# Phaser_1.net
KiCad netlist of a schematic drawn in Altium Designer
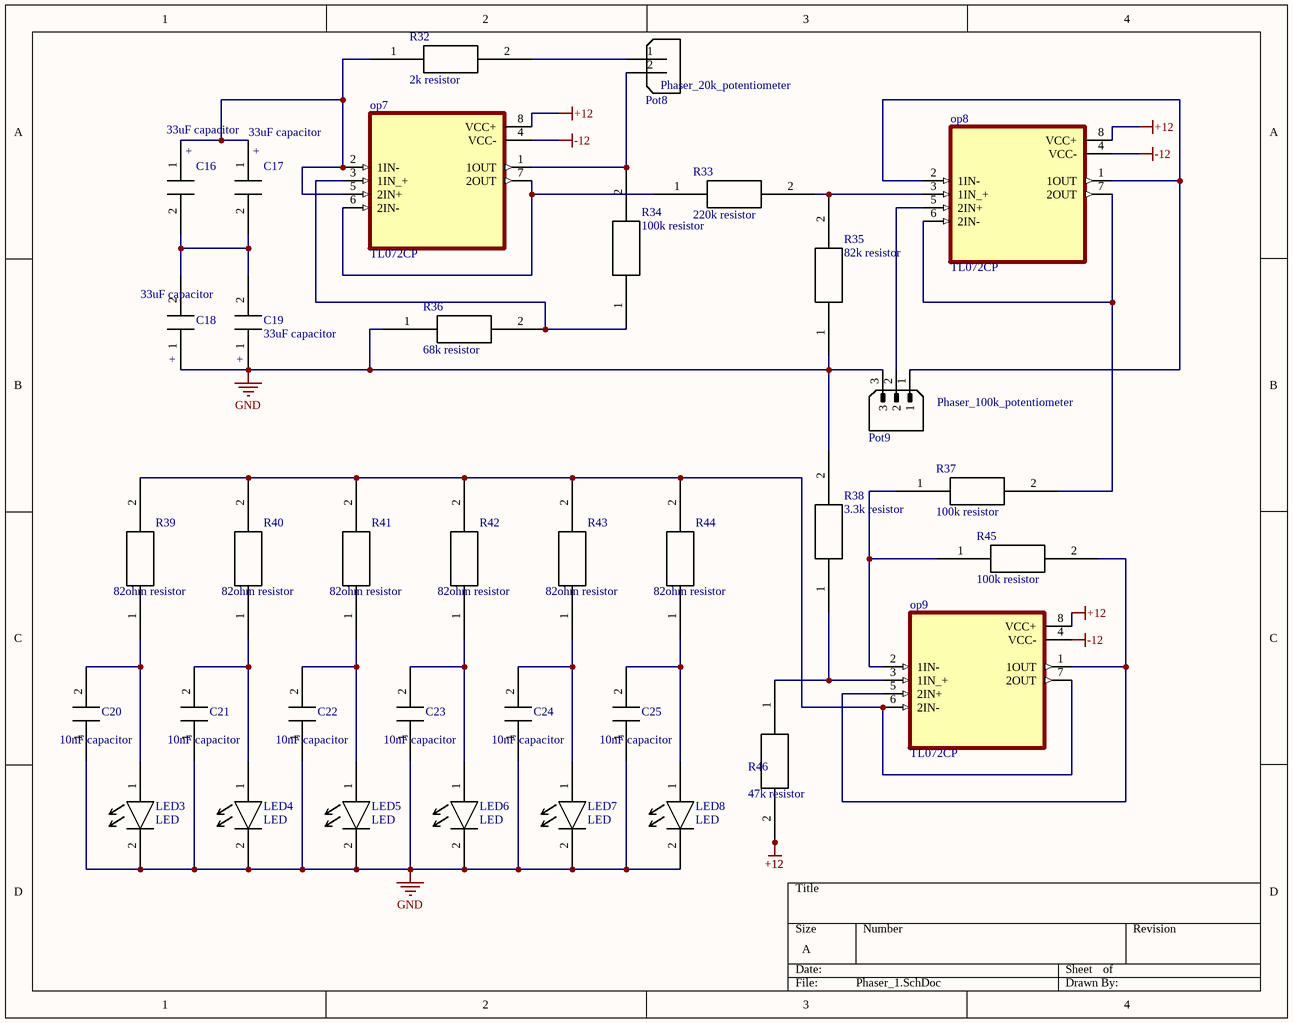
[diagram p0: Phaser_1.SchDoc]

(export (version "E")
  (design (tool "Eeschema 10.0.6"))
  (components
    (comp (ref "C16")
      (value "33uF capacitor")
      (footprint "33uF")
      (libsource (lib "Analog_Project_Schlib") (part "33uF capacitor"))
    )
    (comp (ref "C17")
      (value "33uF capacitor")
      (footprint "33uF")
      (libsource (lib "Analog_Project_Schlib") (part "33uF capacitor"))
    )
    (comp (ref "C18")
      (value "33uF capacitor")
      (footprint "33uF")
      (libsource (lib "Analog_Project_Schlib") (part "33uF capacitor"))
    )
    (comp (ref "C19")
      (value "33uF capacitor")
      (footprint "33uF")
      (libsource (lib "Analog_Project_Schlib") (part "33uF capacitor"))
    )
    (comp (ref "C20")
      (value "10nF capacitor")
      (footprint "10nF")
      (libsource (lib "Analog_Project_Schlib") (part "10nF capacitor"))
    )
    (comp (ref "C21")
      (value "10nF capacitor")
      (footprint "10nF")
      (libsource (lib "Analog_Project_Schlib") (part "10nF capacitor"))
    )
    (comp (ref "C22")
      (value "10nF capacitor")
      (footprint "10nF")
      (libsource (lib "Analog_Project_Schlib") (part "10nF capacitor"))
    )
    (comp (ref "C23")
      (value "10nF capacitor")
      (footprint "10nF")
      (libsource (lib "Analog_Project_Schlib") (part "10nF capacitor"))
    )
    (comp (ref "C24")
      (value "10nF capacitor")
      (footprint "10nF")
      (libsource (lib "Analog_Project_Schlib") (part "10nF capacitor"))
    )
    (comp (ref "C25")
      (value "10nF capacitor")
      (footprint "10nF")
      (libsource (lib "Analog_Project_Schlib") (part "10nF capacitor"))
    )
    (comp (ref "LED3") (value "LED") (footprint "LED") (libsource (lib "Analog_Project_Schlib") (part "LED")))
    (comp (ref "LED4") (value "LED") (footprint "LED") (libsource (lib "Analog_Project_Schlib") (part "LED")))
    (comp (ref "LED5") (value "LED") (footprint "LED") (libsource (lib "Analog_Project_Schlib") (part "LED")))
    (comp (ref "LED6") (value "LED") (footprint "LED") (libsource (lib "Analog_Project_Schlib") (part "LED")))
    (comp (ref "LED7") (value "LED") (footprint "LED") (libsource (lib "Analog_Project_Schlib") (part "LED")))
    (comp (ref "LED8") (value "LED") (footprint "LED") (libsource (lib "Analog_Project_Schlib") (part "LED")))
    (comp (ref "op7")
      (value "TL072CP")
      (footprint "TL072CP")
      (libsource (lib "Analog_Project_Schlib") (part "TL072CP"))
    )
    (comp (ref "op8")
      (value "TL072CP")
      (footprint "TL072CP")
      (libsource (lib "Analog_Project_Schlib") (part "TL072CP"))
    )
    (comp (ref "op9")
      (value "TL072CP")
      (footprint "TL072CP")
      (libsource (lib "Analog_Project_Schlib") (part "TL072CP"))
    )
    (comp (ref "Pot8")
      (value "Phaser_20k_potentiometer")
      (footprint "2pin_JST_non_polarized")
      (libsource (lib "Analog_Project_Schlib") (part "2pin_jst_non_polarized"))
    )
    (comp (ref "Pot9")
      (value "Phaser_100k_potentiometer")
      (footprint "3pin_jst")
      (libsource (lib "Analog_Project_Schlib") (part "3pin_jst"))
    )
    (comp (ref "R32")
      (value "2k resistor")
      (footprint "2k")
      (libsource (lib "Analog_Project_Schlib") (part "2k resistor"))
    )
    (comp (ref "R33")
      (value "220k resistor")
      (footprint "220k")
      (libsource (lib "Analog_Project_Schlib") (part "220k resistor"))
    )
    (comp (ref "R34")
      (value "100k resistor")
      (footprint "100k")
      (libsource (lib "Analog_Project_Schlib") (part "100k resistor"))
    )
    (comp (ref "R35")
      (value "82k resistor")
      (footprint "82k")
      (libsource (lib "Analog_Project_Schlib") (part "82k resistor"))
    )
    (comp (ref "R36")
      (value "68k resistor")
      (footprint "68k")
      (libsource (lib "Analog_Project_Schlib") (part "68k resistor"))
    )
    (comp (ref "R37")
      (value "100k resistor")
      (footprint "100k")
      (libsource (lib "Analog_Project_Schlib") (part "100k resistor"))
    )
    (comp (ref "R38")
      (value "3.3k resistor")
      (footprint "3.3k")
      (libsource (lib "Analog_Project_Schlib") (part "3.3k resistor"))
    )
    (comp (ref "R39")
      (value "82ohm resistor")
      (footprint "82")
      (libsource (lib "Analog_Project_Schlib") (part "82ohm resistor"))
    )
    (comp (ref "R40")
      (value "82ohm resistor")
      (footprint "82")
      (libsource (lib "Analog_Project_Schlib") (part "82ohm resistor"))
    )
    (comp (ref "R41")
      (value "82ohm resistor")
      (footprint "82")
      (libsource (lib "Analog_Project_Schlib") (part "82ohm resistor"))
    )
    (comp (ref "R42")
      (value "82ohm resistor")
      (footprint "82")
      (libsource (lib "Analog_Project_Schlib") (part "82ohm resistor"))
    )
    (comp (ref "R43")
      (value "82ohm resistor")
      (footprint "82")
      (libsource (lib "Analog_Project_Schlib") (part "82ohm resistor"))
    )
    (comp (ref "R44")
      (value "82ohm resistor")
      (footprint "82")
      (libsource (lib "Analog_Project_Schlib") (part "82ohm resistor"))
    )
    (comp (ref "R45")
      (value "100k resistor")
      (footprint "100k")
      (libsource (lib "Analog_Project_Schlib") (part "100k resistor"))
    )
    (comp (ref "R46")
      (value "47k resistor")
      (footprint "47k")
      (libsource (lib "Analog_Project_Schlib") (part "47k resistor"))
    )
  )
  (nets
    (net (code "1") (name "+12") (class "Default")
      (node (ref "R46") (pin "2") (pinfunction "2_2") (pintype "passive"))
      (node (ref "op7") (pin "8") (pinfunction "VCC+_8") (pintype "power_in"))
      (node (ref "op8") (pin "8") (pinfunction "VCC+_8") (pintype "power_in"))
      (node (ref "op9") (pin "8") (pinfunction "VCC+_8") (pintype "power_in"))
    )
    (net (code "2") (name "-12") (class "Default")
      (node (ref "op7") (pin "4") (pinfunction "VCC-_4") (pintype "power_in"))
      (node (ref "op8") (pin "4") (pinfunction "VCC-_4") (pintype "power_in"))
      (node (ref "op9") (pin "4") (pinfunction "VCC-_4") (pintype "power_in"))
    )
    (net (code "3") (name "GND") (class "Default")
      (node (ref "C18") (pin "1") (pinfunction "1_1") (pintype "passive"))
      (node (ref "C19") (pin "1") (pinfunction "1_1") (pintype "passive"))
      (node (ref "C20") (pin "1") (pinfunction "1_1") (pintype "passive"))
      (node (ref "C21") (pin "1") (pinfunction "1_1") (pintype "passive"))
      (node (ref "C22") (pin "1") (pinfunction "1_1") (pintype "passive"))
      (node (ref "C23") (pin "1") (pinfunction "1_1") (pintype "passive"))
      (node (ref "C24") (pin "1") (pinfunction "1_1") (pintype "passive"))
      (node (ref "C25") (pin "1") (pinfunction "1_1") (pintype "passive"))
      (node (ref "LED3") (pin "2") (pinfunction "2_2") (pintype "passive"))
      (node (ref "LED4") (pin "2") (pinfunction "2_2") (pintype "passive"))
      (node (ref "LED5") (pin "2") (pinfunction "2_2") (pintype "passive"))
      (node (ref "LED6") (pin "2") (pinfunction "2_2") (pintype "passive"))
      (node (ref "LED7") (pin "2") (pinfunction "2_2") (pintype "passive"))
      (node (ref "LED8") (pin "2") (pinfunction "2_2") (pintype "passive"))
      (node (ref "Pot9") (pin "3") (pinfunction "3_3") (pintype "passive"))
      (node (ref "R35") (pin "1") (pinfunction "1_1") (pintype "passive"))
      (node (ref "R36") (pin "1") (pinfunction "1_1") (pintype "passive"))
      (node (ref "R38") (pin "2") (pinfunction "2_2") (pintype "passive"))
    )
    (net (code "4") (name "Net-(C16-Pad2)") (class "Default")
      (node (ref "C16") (pin "2") (pinfunction "2_2") (pintype "passive"))
      (node (ref "C17") (pin "2") (pinfunction "2_2") (pintype "passive"))
      (node (ref "C18") (pin "2") (pinfunction "2_2") (pintype "passive"))
      (node (ref "C19") (pin "2") (pinfunction "2_2") (pintype "passive"))
    )
    (net (code "5") (name "Net-(C20-Pad2)") (class "Default")
      (node (ref "C20") (pin "2") (pinfunction "2_2") (pintype "passive"))
      (node (ref "LED3") (pin "1") (pinfunction "1_1") (pintype "passive"))
      (node (ref "R39") (pin "1") (pinfunction "1_1") (pintype "passive"))
    )
    (net (code "6") (name "Net-(C21-Pad2)") (class "Default")
      (node (ref "C21") (pin "2") (pinfunction "2_2") (pintype "passive"))
      (node (ref "LED4") (pin "1") (pinfunction "1_1") (pintype "passive"))
      (node (ref "R40") (pin "1") (pinfunction "1_1") (pintype "passive"))
    )
    (net (code "7") (name "Net-(C22-Pad2)") (class "Default")
      (node (ref "C22") (pin "2") (pinfunction "2_2") (pintype "passive"))
      (node (ref "LED5") (pin "1") (pinfunction "1_1") (pintype "passive"))
      (node (ref "R41") (pin "1") (pinfunction "1_1") (pintype "passive"))
    )
    (net (code "8") (name "Net-(C23-Pad2)") (class "Default")
      (node (ref "C23") (pin "2") (pinfunction "2_2") (pintype "passive"))
      (node (ref "LED6") (pin "1") (pinfunction "1_1") (pintype "passive"))
      (node (ref "R42") (pin "1") (pinfunction "1_1") (pintype "passive"))
    )
    (net (code "9") (name "Net-(C24-Pad2)") (class "Default")
      (node (ref "C24") (pin "2") (pinfunction "2_2") (pintype "passive"))
      (node (ref "LED7") (pin "1") (pinfunction "1_1") (pintype "passive"))
      (node (ref "R43") (pin "1") (pinfunction "1_1") (pintype "passive"))
    )
    (net (code "10") (name "Net-(C25-Pad2)") (class "Default")
      (node (ref "C25") (pin "2") (pinfunction "2_2") (pintype "passive"))
      (node (ref "LED8") (pin "1") (pinfunction "1_1") (pintype "passive"))
      (node (ref "R44") (pin "1") (pinfunction "1_1") (pintype "passive"))
    )
    (net (code "11") (name "Net-(Pot8-Pad1)") (class "Default")
      (node (ref "Pot8") (pin "1") (pinfunction "1_1") (pintype "passive"))
      (node (ref "R32") (pin "2") (pinfunction "2_2") (pintype "passive"))
    )
    (net (code "12") (name "Net-(op7-1IN-)") (class "Default")
      (node (ref "C16") (pin "1") (pinfunction "1_1") (pintype "passive"))
      (node (ref "C17") (pin "1") (pinfunction "1_1") (pintype "passive"))
      (node (ref "R32") (pin "1") (pinfunction "1_1") (pintype "passive"))
      (node (ref "op7") (pin "2") (pinfunction "1IN-_2") (pintype "input"))
      (node (ref "op7") (pin "5") (pinfunction "2IN+_5") (pintype "input"))
    )
    (net (code "13") (name "Net-(op7-1IN_+)") (class "Default")
      (node (ref "R34") (pin "1") (pinfunction "1_1") (pintype "passive"))
      (node (ref "R36") (pin "2") (pinfunction "2_2") (pintype "passive"))
      (node (ref "op7") (pin "3") (pinfunction "1IN_+_3") (pintype "input"))
    )
    (net (code "14") (name "Net-(op7-1OUT)") (class "Default")
      (node (ref "Pot8") (pin "2") (pinfunction "2_2") (pintype "passive"))
      (node (ref "R34") (pin "2") (pinfunction "2_2") (pintype "passive"))
      (node (ref "op7") (pin "1") (pinfunction "1OUT_1") (pintype "output"))
    )
    (net (code "15") (name "Net-(op7-2IN-)") (class "Default")
      (node (ref "R33") (pin "1") (pinfunction "1_1") (pintype "passive"))
      (node (ref "op7") (pin "6") (pinfunction "2IN-_6") (pintype "input"))
      (node (ref "op7") (pin "7") (pinfunction "2OUT_7") (pintype "output"))
    )
    (net (code "16") (name "Net-(op8-1IN-)") (class "Default")
      (node (ref "Pot9") (pin "1") (pinfunction "1_1") (pintype "passive"))
      (node (ref "op8") (pin "1") (pinfunction "1OUT_1") (pintype "output"))
      (node (ref "op8") (pin "2") (pinfunction "1IN-_2") (pintype "input"))
    )
    (net (code "17") (name "Net-(op8-1IN_+)") (class "Default")
      (node (ref "R33") (pin "2") (pinfunction "2_2") (pintype "passive"))
      (node (ref "R35") (pin "2") (pinfunction "2_2") (pintype "passive"))
      (node (ref "op8") (pin "3") (pinfunction "1IN_+_3") (pintype "input"))
    )
    (net (code "18") (name "Net-(op8-2IN+)") (class "Default")
      (node (ref "Pot9") (pin "2") (pinfunction "2_2") (pintype "passive"))
      (node (ref "op8") (pin "5") (pinfunction "2IN+_5") (pintype "input"))
    )
    (net (code "19") (name "Net-(op8-2IN-)") (class "Default")
      (node (ref "R37") (pin "2") (pinfunction "2_2") (pintype "passive"))
      (node (ref "op8") (pin "6") (pinfunction "2IN-_6") (pintype "input"))
      (node (ref "op8") (pin "7") (pinfunction "2OUT_7") (pintype "output"))
    )
    (net (code "20") (name "Net-(op9-1IN-)") (class "Default")
      (node (ref "R37") (pin "1") (pinfunction "1_1") (pintype "passive"))
      (node (ref "R45") (pin "1") (pinfunction "1_1") (pintype "passive"))
      (node (ref "op9") (pin "2") (pinfunction "1IN-_2") (pintype "input"))
    )
    (net (code "21") (name "Net-(op9-1IN_+)") (class "Default")
      (node (ref "R38") (pin "1") (pinfunction "1_1") (pintype "passive"))
      (node (ref "R46") (pin "1") (pinfunction "1_1") (pintype "passive"))
      (node (ref "op9") (pin "3") (pinfunction "1IN_+_3") (pintype "input"))
    )
    (net (code "22") (name "Net-(op9-1OUT)") (class "Default")
      (node (ref "R45") (pin "2") (pinfunction "2_2") (pintype "passive"))
      (node (ref "op9") (pin "1") (pinfunction "1OUT_1") (pintype "output"))
      (node (ref "op9") (pin "5") (pinfunction "2IN+_5") (pintype "input"))
    )
    (net (code "23") (name "Net-(op9-2IN-)") (class "Default")
      (node (ref "R39") (pin "2") (pinfunction "2_2") (pintype "passive"))
      (node (ref "R40") (pin "2") (pinfunction "2_2") (pintype "passive"))
      (node (ref "R41") (pin "2") (pinfunction "2_2") (pintype "passive"))
      (node (ref "R42") (pin "2") (pinfunction "2_2") (pintype "passive"))
      (node (ref "R43") (pin "2") (pinfunction "2_2") (pintype "passive"))
      (node (ref "R44") (pin "2") (pinfunction "2_2") (pintype "passive"))
      (node (ref "op9") (pin "6") (pinfunction "2IN-_6") (pintype "input"))
      (node (ref "op9") (pin "7") (pinfunction "2OUT_7") (pintype "output"))
    )
  )
)
